# Sport_Analyzer_Teensy4.net
KiCad netlist of a schematic drawn in EAGLE
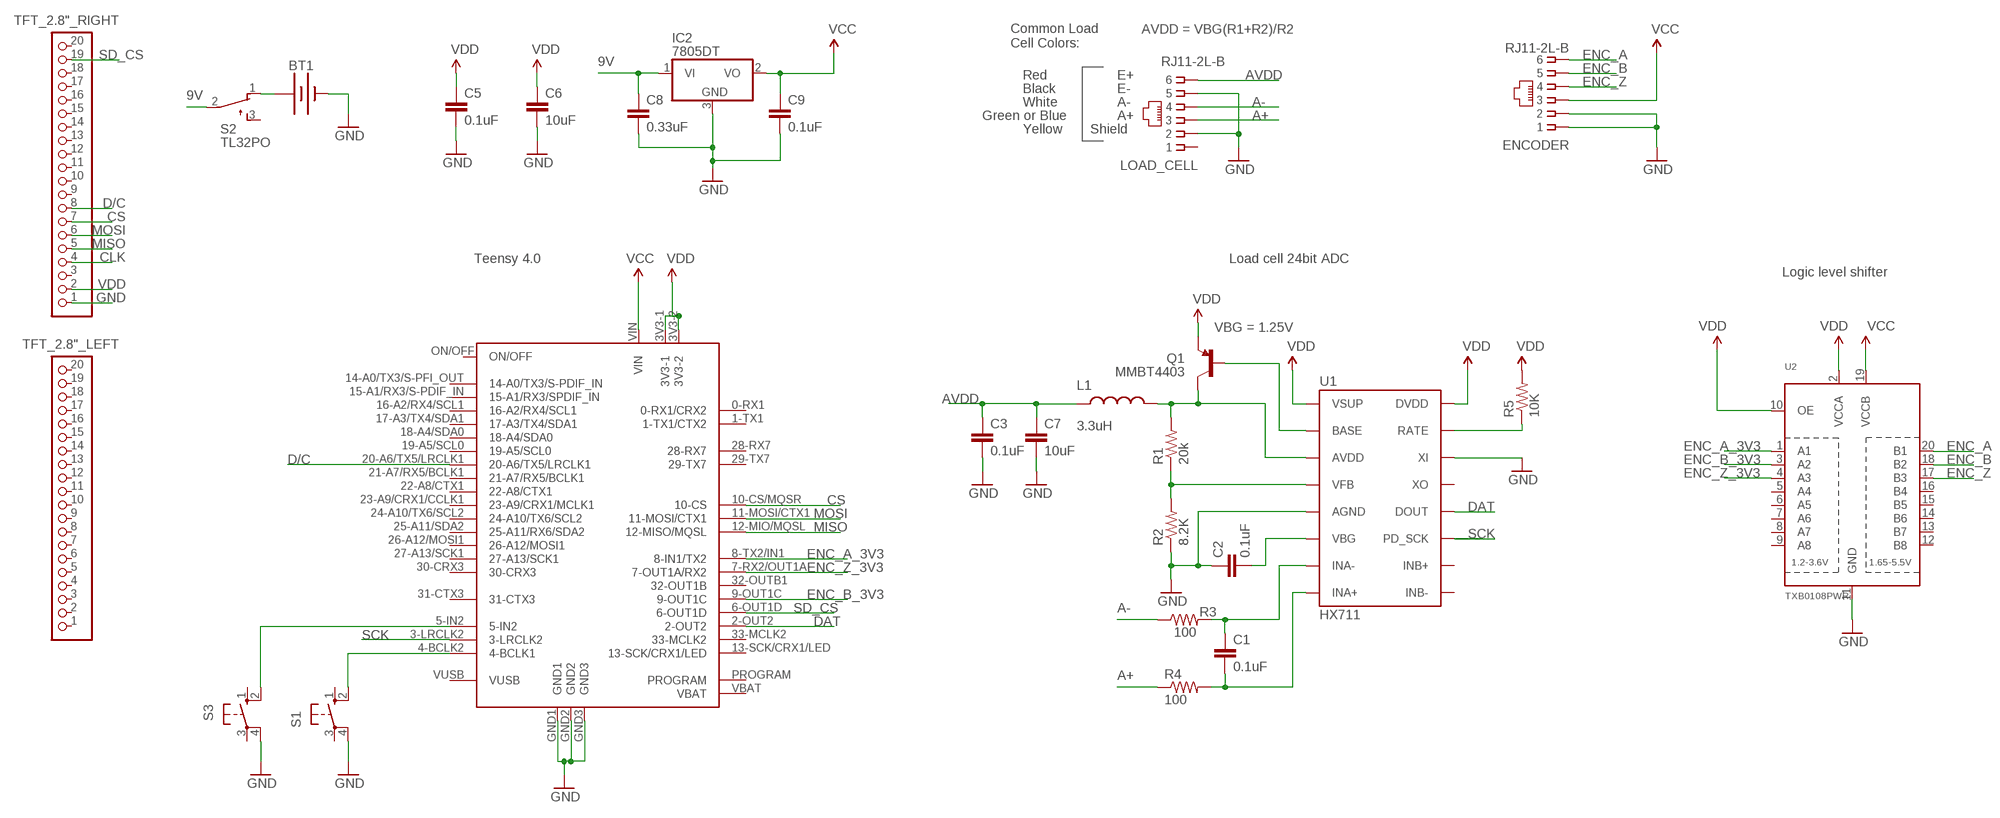
[diagram p0: schematic, sheet 1]

(export (version "E")
  (design (tool "Eeschema 10.0.6"))
  (components
    (comp (ref "BT1")
      (value "BATTERY-9V")
      (footprint "eagle-import:BATTCON_9V")
      (libsource (lib "eagle-import") (part "BATTERY-9V"))
    )
    (comp (ref "C1")
      (value "0.1uF")
      (footprint "eagle-import:0603-CAP")
      (libsource (lib "eagle-import") (part "0.1UF-25V-5%(0603)"))
    )
    (comp (ref "C2")
      (value "0.1uF")
      (footprint "eagle-import:0603-CAP")
      (libsource (lib "eagle-import") (part "0.1UF-25V-5%(0603)"))
    )
    (comp (ref "C3")
      (value "0.1uF")
      (footprint "eagle-import:0603-CAP")
      (libsource (lib "eagle-import") (part "0.1UF-25V-5%(0603)"))
    )
    (comp (ref "C5")
      (value "0.1uF")
      (footprint "eagle-import:0603-CAP")
      (libsource (lib "eagle-import") (part "0.1UF-25V-5%(0603)"))
    )
    (comp (ref "C6")
      (value "10uF")
      (footprint "eagle-import:1210")
      (libsource (lib "eagle-import") (part "10UF50V20%(1210)"))
    )
    (comp (ref "C7")
      (value "10uF")
      (footprint "eagle-import:1210")
      (libsource (lib "eagle-import") (part "10UF50V20%(1210)"))
    )
    (comp (ref "C8")
      (value "0.33uF")
      (footprint "eagle-import:0603-CAP")
      (libsource (lib "eagle-import") (part "0.1UF-25V-5%(0603)"))
    )
    (comp (ref "C9")
      (value "0.1uF")
      (footprint "eagle-import:0603-CAP")
      (libsource (lib "eagle-import") (part "0.1UF-25V-5%(0603)"))
    )
    (comp (ref "ENCODER")
      (value "RJ11-2L-B")
      (footprint "eagle-import:RJ11-NO_SHIELD")
      (fields (field (name "MF") "TYCO ELECTRONICS"))
      (libsource (lib "eagle-import") (part "RJ11-2L-B"))
    )
    (comp (ref "IC2")
      (value "7805DT")
      (footprint "eagle-import:TO252")
      (libsource (lib "eagle-import") (part "78DT05"))
    )
    (comp (ref "L1")
      (value "3.3uH")
      (footprint "eagle-import:0805")
      (libsource (lib "eagle-import") (part "INDUCTOR0805-IND"))
    )
    (comp (ref "LOAD_CELL")
      (value "RJ11-2L-B")
      (footprint "eagle-import:RJ11-NO_SHIELD")
      (fields (field (name "MF") "TYCO ELECTRONICS"))
      (libsource (lib "eagle-import") (part "RJ11-2L-B"))
    )
    (comp (ref "Q1")
      (value "MMBT4403")
      (footprint "eagle-import:SOT23-3")
      (libsource (lib "eagle-import") (part "TRANSISTOR_PNPMMBT4403"))
    )
    (comp (ref "R1")
      (value "20k")
      (footprint "eagle-import:0603-RES")
      (libsource (lib "eagle-import") (part "20KOHM1/10W1%(0603)"))
    )
    (comp (ref "R2")
      (value "8.2K")
      (footprint "eagle-import:0603-RES")
      (libsource (lib "eagle-import") (part "8.2KOHM-1/10W-5%(0603)"))
    )
    (comp (ref "R3")
      (value "100")
      (footprint "eagle-import:0603-RES")
      (libsource (lib "eagle-import") (part "100OHM-1/10W-1%(0603)"))
    )
    (comp (ref "R4")
      (value "100")
      (footprint "eagle-import:0603-RES")
      (libsource (lib "eagle-import") (part "100OHM-1/10W-1%(0603)"))
    )
    (comp (ref "R5")
      (value "10K")
      (footprint "eagle-import:0603-RES")
      (libsource (lib "eagle-import") (part "10KOHM-1/10W-1%(0603)0603"))
    )
    (comp (ref "S1")
      (value "10-XX")
      (footprint "eagle-import:B3F-10XX")
      (fields (field (name "MPN") "B3F-1000"))
      (libsource (lib "eagle-import") (part "10-XX"))
    )
    (comp (ref "S2")
      (value "TL32PO")
      (footprint "eagle-import:TL3XPO")
      (libsource (lib "eagle-import") (part "TL32PO"))
    )
    (comp (ref "S3")
      (value "10-XX")
      (footprint "eagle-import:B3F-10XX")
      (fields (field (name "MPN") "B3F-1000"))
      (libsource (lib "eagle-import") (part "10-XX"))
    )
    (comp (ref "TFT_2.8\"_LEFT")
      (value "PINHD-1X20")
      (footprint "eagle-import:1X20")
      (libsource (lib "eagle-import") (part "PINHD-1X20"))
    )
    (comp (ref "TFT_2.8\"_RIGHT")
      (value "PINHD-1X20")
      (footprint "eagle-import:1X20")
      (libsource (lib "eagle-import") (part "PINHD-1X20"))
    )
    (comp (ref "U$2")
      (value "TEENSY40")
      (footprint "eagle-import:TEENSY40")
      (libsource (lib "eagle-import") (part "TEENSY40"))
    )
    (comp (ref "U1")
      (value "HX711")
      (footprint "eagle-import:SO16")
      (libsource (lib "eagle-import") (part "HX711HX711"))
    )
    (comp (ref "U2")
      (value "TXB0108PWR")
      (footprint "eagle-import:TSSOP20")
      (libsource (lib "eagle-import") (part "TXB0108PWR"))
    )
  )
  (nets
    (net (code "1") (name "/9V") (class "Default")
      (node (ref "C8") (pin "1") (pinfunction "1_1") (pintype "passive"))
      (node (ref "IC2") (pin "1") (pinfunction "VI_1") (pintype "input"))
      (node (ref "S2") (pin "2") (pinfunction "P_2") (pintype "passive"))
    )
    (net (code "2") (name "/A+") (class "Default")
      (node (ref "LOAD_CELL") (pin "3") (pinfunction "3_3") (pintype "passive"))
      (node (ref "R4") (pin "1") (pinfunction "1_1") (pintype "passive"))
    )
    (net (code "3") (name "/A-") (class "Default")
      (node (ref "LOAD_CELL") (pin "4") (pinfunction "4_4") (pintype "passive"))
      (node (ref "R3") (pin "1") (pinfunction "1_1") (pintype "passive"))
    )
    (net (code "4") (name "/AVDD") (class "Default")
      (node (ref "C3") (pin "1") (pinfunction "1_1") (pintype "passive"))
      (node (ref "C7") (pin "1") (pinfunction "1_1") (pintype "passive"))
      (node (ref "L1") (pin "1") (pinfunction "1_1") (pintype "passive"))
      (node (ref "LOAD_CELL") (pin "6") (pinfunction "6_6") (pintype "passive"))
    )
    (net (code "5") (name "/CLK") (class "Default")
      (node (ref "TFT_2.8\"_RIGHT") (pin "4") (pinfunction "4_4") (pintype "passive"))
    )
    (net (code "6") (name "/CS") (class "Default")
      (node (ref "TFT_2.8\"_RIGHT") (pin "7") (pinfunction "7_7") (pintype "passive"))
      (node (ref "U$2") (pin "10-CS/MQSR") (pinfunction "10-CS_10-CS/MQSR") (pintype "bidirectional"))
    )
    (net (code "7") (name "/DAT") (class "Default")
      (node (ref "U$2") (pin "2-OUT2") (pinfunction "2-OUT2_2-OUT2") (pintype "bidirectional"))
      (node (ref "U1") (pin "12") (pinfunction "DOUT_12") (pintype "bidirectional"))
    )
    (net (code "8") (name "/D{slash}C") (class "Default")
      (node (ref "TFT_2.8\"_RIGHT") (pin "8") (pinfunction "8_8") (pintype "passive"))
      (node (ref "U$2") (pin "20-A6/TX5/LRCLK1") (pinfunction "20-A6/TX5/LRCLK1_20-A6/TX5/LRCLK1") (pintype "bidirectional"))
    )
    (net (code "9") (name "/ENC_A") (class "Default")
      (node (ref "ENCODER") (pin "6") (pinfunction "6_6") (pintype "passive"))
      (node (ref "U2") (pin "20") (pinfunction "B1_20") (pintype "bidirectional"))
    )
    (net (code "10") (name "/ENC_A_3V3") (class "Default")
      (node (ref "U$2") (pin "8-TX2/IN1") (pinfunction "8-IN1/TX2_8-TX2/IN1") (pintype "bidirectional"))
      (node (ref "U2") (pin "1") (pinfunction "A1_1") (pintype "bidirectional"))
    )
    (net (code "11") (name "/ENC_B") (class "Default")
      (node (ref "ENCODER") (pin "5") (pinfunction "5_5") (pintype "passive"))
      (node (ref "U2") (pin "18") (pinfunction "B2_18") (pintype "bidirectional"))
    )
    (net (code "12") (name "/ENC_B_3V3") (class "Default")
      (node (ref "U$2") (pin "9-OUT1C") (pinfunction "9-OUT1C_9-OUT1C") (pintype "bidirectional"))
      (node (ref "U2") (pin "3") (pinfunction "A2_3") (pintype "bidirectional"))
    )
    (net (code "13") (name "/ENC_Z") (class "Default")
      (node (ref "ENCODER") (pin "4") (pinfunction "4_4") (pintype "passive"))
      (node (ref "U2") (pin "17") (pinfunction "B3_17") (pintype "bidirectional"))
    )
    (net (code "14") (name "/ENC_Z_3V3") (class "Default")
      (node (ref "U$2") (pin "7-RX2/OUT1A") (pinfunction "7-OUT1A/RX2_7-RX2/OUT1A") (pintype "bidirectional"))
      (node (ref "U2") (pin "4") (pinfunction "A3_4") (pintype "bidirectional"))
    )
    (net (code "15") (name "/MISO") (class "Default")
      (node (ref "TFT_2.8\"_RIGHT") (pin "5") (pinfunction "5_5") (pintype "passive"))
      (node (ref "U$2") (pin "12-MIO/MQSL") (pinfunction "12-MISO/MQSL_12-MIO/MQSL") (pintype "bidirectional"))
    )
    (net (code "16") (name "/MOSI") (class "Default")
      (node (ref "TFT_2.8\"_RIGHT") (pin "6") (pinfunction "6_6") (pintype "passive"))
      (node (ref "U$2") (pin "11-MOSI/CTX1") (pinfunction "11-MOSI/CTX1_11-MOSI/CTX1") (pintype "bidirectional"))
    )
    (net (code "17") (name "/SCK") (class "Default")
      (node (ref "U$2") (pin "3-LRCLK2") (pinfunction "3-LRCLK2_3-LRCLK2") (pintype "bidirectional"))
      (node (ref "U1") (pin "11") (pinfunction "PD_SCK_11") (pintype "bidirectional"))
    )
    (net (code "18") (name "/SD_CS") (class "Default")
      (node (ref "TFT_2.8\"_RIGHT") (pin "19") (pinfunction "19_19") (pintype "passive"))
      (node (ref "U$2") (pin "6-OUT1D") (pinfunction "6-OUT1D_6-OUT1D") (pintype "bidirectional"))
    )
    (net (code "19") (name "GND") (class "Default")
      (node (ref "BT1") (pin "-") (pinfunction "-_-") (pintype "power_in"))
      (node (ref "C2") (pin "1") (pinfunction "1_1") (pintype "passive"))
      (node (ref "C3") (pin "2") (pinfunction "2_2") (pintype "passive"))
      (node (ref "C5") (pin "2") (pinfunction "2_2") (pintype "passive"))
      (node (ref "C6") (pin "2") (pinfunction "2_2") (pintype "passive"))
      (node (ref "C7") (pin "2") (pinfunction "2_2") (pintype "passive"))
      (node (ref "C8") (pin "2") (pinfunction "2_2") (pintype "passive"))
      (node (ref "C9") (pin "2") (pinfunction "2_2") (pintype "passive"))
      (node (ref "ENCODER") (pin "1") (pinfunction "1_1") (pintype "passive"))
      (node (ref "ENCODER") (pin "2") (pinfunction "2_2") (pintype "passive"))
      (node (ref "IC2") (pin "3") (pinfunction "GND_3") (pintype "passive"))
      (node (ref "LOAD_CELL") (pin "2") (pinfunction "2_2") (pintype "passive"))
      (node (ref "LOAD_CELL") (pin "5") (pinfunction "5_5") (pintype "passive"))
      (node (ref "R2") (pin "1") (pinfunction "1_1") (pintype "passive"))
      (node (ref "S1") (pin "4") (pinfunction "P1_4") (pintype "passive"))
      (node (ref "S3") (pin "4") (pinfunction "P1_4") (pintype "passive"))
      (node (ref "TFT_2.8\"_RIGHT") (pin "1") (pinfunction "1_1") (pintype "passive"))
      (node (ref "U$2") (pin "GND1") (pinfunction "GND1_GND1") (pintype "bidirectional"))
      (node (ref "U$2") (pin "GND2") (pinfunction "GND2_GND2") (pintype "bidirectional"))
      (node (ref "U$2") (pin "GND3") (pinfunction "GND3_GND3") (pintype "bidirectional"))
      (node (ref "U1") (pin "14") (pinfunction "XI_14") (pintype "bidirectional"))
      (node (ref "U1") (pin "5") (pinfunction "AGND_5") (pintype "bidirectional"))
      (node (ref "U2") (pin "11") (pinfunction "GND_11") (pintype "bidirectional"))
    )
    (net (code "20") (name "Net-(Q1-B)") (class "Default")
      (node (ref "Q1") (pin "1") (pinfunction "B_1") (pintype "passive"))
      (node (ref "U1") (pin "2") (pinfunction "BASE_2") (pintype "bidirectional"))
    )
    (net (code "21") (name "Net-(Q1-C)") (class "Default")
      (node (ref "L1") (pin "2") (pinfunction "2_2") (pintype "passive"))
      (node (ref "Q1") (pin "3") (pinfunction "C_3") (pintype "passive"))
      (node (ref "R1") (pin "2") (pinfunction "2_2") (pintype "passive"))
      (node (ref "U1") (pin "3") (pinfunction "AVDD_3") (pintype "bidirectional"))
    )
    (net (code "22") (name "Net-(S1-S1)") (class "Default")
      (node (ref "S1") (pin "2") (pinfunction "S1_2") (pintype "passive"))
      (node (ref "U$2") (pin "4-BCLK2") (pinfunction "4-BCLK1_4-BCLK2") (pintype "bidirectional"))
    )
    (net (code "23") (name "Net-(S2-O)") (class "Default")
      (node (ref "BT1") (pin "+") (pinfunction "+_+") (pintype "power_in"))
      (node (ref "S2") (pin "1") (pinfunction "O_1") (pintype "passive"))
    )
    (net (code "24") (name "Net-(S3-S1)") (class "Default")
      (node (ref "S3") (pin "2") (pinfunction "S1_2") (pintype "passive"))
      (node (ref "U$2") (pin "5-IN2") (pinfunction "5-IN2_5-IN2") (pintype "bidirectional"))
    )
    (net (code "25") (name "Net-(U1-INA+)") (class "Default")
      (node (ref "C1") (pin "2") (pinfunction "2_2") (pintype "passive"))
      (node (ref "R4") (pin "2") (pinfunction "2_2") (pintype "passive"))
      (node (ref "U1") (pin "8") (pinfunction "INA+_8") (pintype "bidirectional"))
    )
    (net (code "26") (name "Net-(U1-INA-)") (class "Default")
      (node (ref "C1") (pin "1") (pinfunction "1_1") (pintype "passive"))
      (node (ref "R3") (pin "2") (pinfunction "2_2") (pintype "passive"))
      (node (ref "U1") (pin "7") (pinfunction "INA-_7") (pintype "bidirectional"))
    )
    (net (code "27") (name "Net-(U1-RATE)") (class "Default")
      (node (ref "R5") (pin "1") (pinfunction "1_1") (pintype "passive"))
      (node (ref "U1") (pin "15") (pinfunction "RATE_15") (pintype "bidirectional"))
    )
    (net (code "28") (name "Net-(U1-VBG)") (class "Default")
      (node (ref "C2") (pin "2") (pinfunction "2_2") (pintype "passive"))
      (node (ref "U1") (pin "6") (pinfunction "VBG_6") (pintype "bidirectional"))
    )
    (net (code "29") (name "Net-(U1-VFB)") (class "Default")
      (node (ref "R1") (pin "1") (pinfunction "1_1") (pintype "passive"))
      (node (ref "R2") (pin "2") (pinfunction "2_2") (pintype "passive"))
      (node (ref "U1") (pin "4") (pinfunction "VFB_4") (pintype "bidirectional"))
    )
    (net (code "30") (name "VCC") (class "Default")
      (node (ref "C9") (pin "1") (pinfunction "1_1") (pintype "passive"))
      (node (ref "ENCODER") (pin "3") (pinfunction "3_3") (pintype "passive"))
      (node (ref "IC2") (pin "2") (pinfunction "VO_2") (pintype "passive"))
      (node (ref "U$2") (pin "VIN") (pinfunction "VIN_VIN") (pintype "bidirectional"))
      (node (ref "U2") (pin "19") (pinfunction "VCCB_19") (pintype "bidirectional"))
    )
    (net (code "31") (name "VDD") (class "Default")
      (node (ref "C5") (pin "1") (pinfunction "1_1") (pintype "passive"))
      (node (ref "C6") (pin "1") (pinfunction "1_1") (pintype "passive"))
      (node (ref "Q1") (pin "2") (pinfunction "E_2") (pintype "passive"))
      (node (ref "R5") (pin "2") (pinfunction "2_2") (pintype "passive"))
      (node (ref "TFT_2.8\"_RIGHT") (pin "2") (pinfunction "2_2") (pintype "passive"))
      (node (ref "U$2") (pin "3V3-1") (pinfunction "3V3-1_3V3-1") (pintype "bidirectional"))
      (node (ref "U$2") (pin "3V3-2") (pinfunction "3V3-2_3V3-2") (pintype "bidirectional"))
      (node (ref "U1") (pin "1") (pinfunction "VSUP_1") (pintype "bidirectional"))
      (node (ref "U1") (pin "16") (pinfunction "DVDD_16") (pintype "bidirectional"))
      (node (ref "U2") (pin "10") (pinfunction "OE_10") (pintype "bidirectional"))
      (node (ref "U2") (pin "2") (pinfunction "VCCA_2") (pintype "bidirectional"))
    )
    (net (code "32") (name "unconnected-(LOAD_CELL-Pad1)") (class "Default")
      (node (ref "LOAD_CELL") (pin "1") (pinfunction "1_1") (pintype "passive"))
    )
    (net (code "33") (name "unconnected-(S1-P-Pad3)") (class "Default")
      (node (ref "S1") (pin "3") (pinfunction "P_3") (pintype "passive"))
    )
    (net (code "34") (name "unconnected-(S1-S-Pad1)") (class "Default")
      (node (ref "S1") (pin "1") (pinfunction "S_1") (pintype "passive"))
    )
    (net (code "35") (name "unconnected-(S2-S-Pad3)") (class "Default")
      (node (ref "S2") (pin "3") (pinfunction "S_3") (pintype "passive"))
    )
    (net (code "36") (name "unconnected-(S3-P-Pad3)") (class "Default")
      (node (ref "S3") (pin "3") (pinfunction "P_3") (pintype "passive"))
    )
    (net (code "37") (name "unconnected-(S3-S-Pad1)") (class "Default")
      (node (ref "S3") (pin "1") (pinfunction "S_1") (pintype "passive"))
    )
    (net (code "38") (name "unconnected-(TFT_2.8\"_LEFT-Pad1)") (class "Default")
      (node (ref "TFT_2.8\"_LEFT") (pin "1") (pinfunction "1_1") (pintype "passive"))
    )
    (net (code "39") (name "unconnected-(TFT_2.8\"_LEFT-Pad2)") (class "Default")
      (node (ref "TFT_2.8\"_LEFT") (pin "2") (pinfunction "2_2") (pintype "passive"))
    )
    (net (code "40") (name "unconnected-(TFT_2.8\"_LEFT-Pad3)") (class "Default")
      (node (ref "TFT_2.8\"_LEFT") (pin "3") (pinfunction "3_3") (pintype "passive"))
    )
    (net (code "41") (name "unconnected-(TFT_2.8\"_LEFT-Pad4)") (class "Default")
      (node (ref "TFT_2.8\"_LEFT") (pin "4") (pinfunction "4_4") (pintype "passive"))
    )
    (net (code "42") (name "unconnected-(TFT_2.8\"_LEFT-Pad5)") (class "Default")
      (node (ref "TFT_2.8\"_LEFT") (pin "5") (pinfunction "5_5") (pintype "passive"))
    )
    (net (code "43") (name "unconnected-(TFT_2.8\"_LEFT-Pad6)") (class "Default")
      (node (ref "TFT_2.8\"_LEFT") (pin "6") (pinfunction "6_6") (pintype "passive"))
    )
    (net (code "44") (name "unconnected-(TFT_2.8\"_LEFT-Pad7)") (class "Default")
      (node (ref "TFT_2.8\"_LEFT") (pin "7") (pinfunction "7_7") (pintype "passive"))
    )
    (net (code "45") (name "unconnected-(TFT_2.8\"_LEFT-Pad8)") (class "Default")
      (node (ref "TFT_2.8\"_LEFT") (pin "8") (pinfunction "8_8") (pintype "passive"))
    )
    (net (code "46") (name "unconnected-(TFT_2.8\"_LEFT-Pad9)") (class "Default")
      (node (ref "TFT_2.8\"_LEFT") (pin "9") (pinfunction "9_9") (pintype "passive"))
    )
    (net (code "47") (name "unconnected-(TFT_2.8\"_LEFT-Pad10)") (class "Default")
      (node (ref "TFT_2.8\"_LEFT") (pin "10") (pinfunction "10_10") (pintype "passive"))
    )
    (net (code "48") (name "unconnected-(TFT_2.8\"_LEFT-Pad11)") (class "Default")
      (node (ref "TFT_2.8\"_LEFT") (pin "11") (pinfunction "11_11") (pintype "passive"))
    )
    (net (code "49") (name "unconnected-(TFT_2.8\"_LEFT-Pad12)") (class "Default")
      (node (ref "TFT_2.8\"_LEFT") (pin "12") (pinfunction "12_12") (pintype "passive"))
    )
    (net (code "50") (name "unconnected-(TFT_2.8\"_LEFT-Pad13)") (class "Default")
      (node (ref "TFT_2.8\"_LEFT") (pin "13") (pinfunction "13_13") (pintype "passive"))
    )
    (net (code "51") (name "unconnected-(TFT_2.8\"_LEFT-Pad14)") (class "Default")
      (node (ref "TFT_2.8\"_LEFT") (pin "14") (pinfunction "14_14") (pintype "passive"))
    )
    (net (code "52") (name "unconnected-(TFT_2.8\"_LEFT-Pad15)") (class "Default")
      (node (ref "TFT_2.8\"_LEFT") (pin "15") (pinfunction "15_15") (pintype "passive"))
    )
    (net (code "53") (name "unconnected-(TFT_2.8\"_LEFT-Pad16)") (class "Default")
      (node (ref "TFT_2.8\"_LEFT") (pin "16") (pinfunction "16_16") (pintype "passive"))
    )
    (net (code "54") (name "unconnected-(TFT_2.8\"_LEFT-Pad17)") (class "Default")
      (node (ref "TFT_2.8\"_LEFT") (pin "17") (pinfunction "17_17") (pintype "passive"))
    )
    (net (code "55") (name "unconnected-(TFT_2.8\"_LEFT-Pad18)") (class "Default")
      (node (ref "TFT_2.8\"_LEFT") (pin "18") (pinfunction "18_18") (pintype "passive"))
    )
    (net (code "56") (name "unconnected-(TFT_2.8\"_LEFT-Pad19)") (class "Default")
      (node (ref "TFT_2.8\"_LEFT") (pin "19") (pinfunction "19_19") (pintype "passive"))
    )
    (net (code "57") (name "unconnected-(TFT_2.8\"_LEFT-Pad20)") (class "Default")
      (node (ref "TFT_2.8\"_LEFT") (pin "20") (pinfunction "20_20") (pintype "passive"))
    )
    (net (code "58") (name "unconnected-(TFT_2.8\"_RIGHT-Pad3)") (class "Default")
      (node (ref "TFT_2.8\"_RIGHT") (pin "3") (pinfunction "3_3") (pintype "passive"))
    )
    (net (code "59") (name "unconnected-(TFT_2.8\"_RIGHT-Pad9)") (class "Default")
      (node (ref "TFT_2.8\"_RIGHT") (pin "9") (pinfunction "9_9") (pintype "passive"))
    )
    (net (code "60") (name "unconnected-(TFT_2.8\"_RIGHT-Pad10)") (class "Default")
      (node (ref "TFT_2.8\"_RIGHT") (pin "10") (pinfunction "10_10") (pintype "passive"))
    )
    (net (code "61") (name "unconnected-(TFT_2.8\"_RIGHT-Pad11)") (class "Default")
      (node (ref "TFT_2.8\"_RIGHT") (pin "11") (pinfunction "11_11") (pintype "passive"))
    )
    (net (code "62") (name "unconnected-(TFT_2.8\"_RIGHT-Pad12)") (class "Default")
      (node (ref "TFT_2.8\"_RIGHT") (pin "12") (pinfunction "12_12") (pintype "passive"))
    )
    (net (code "63") (name "unconnected-(TFT_2.8\"_RIGHT-Pad13)") (class "Default")
      (node (ref "TFT_2.8\"_RIGHT") (pin "13") (pinfunction "13_13") (pintype "passive"))
    )
    (net (code "64") (name "unconnected-(TFT_2.8\"_RIGHT-Pad14)") (class "Default")
      (node (ref "TFT_2.8\"_RIGHT") (pin "14") (pinfunction "14_14") (pintype "passive"))
    )
    (net (code "65") (name "unconnected-(TFT_2.8\"_RIGHT-Pad15)") (class "Default")
      (node (ref "TFT_2.8\"_RIGHT") (pin "15") (pinfunction "15_15") (pintype "passive"))
    )
    (net (code "66") (name "unconnected-(TFT_2.8\"_RIGHT-Pad16)") (class "Default")
      (node (ref "TFT_2.8\"_RIGHT") (pin "16") (pinfunction "16_16") (pintype "passive"))
    )
    (net (code "67") (name "unconnected-(TFT_2.8\"_RIGHT-Pad17)") (class "Default")
      (node (ref "TFT_2.8\"_RIGHT") (pin "17") (pinfunction "17_17") (pintype "passive"))
    )
    (net (code "68") (name "unconnected-(TFT_2.8\"_RIGHT-Pad18)") (class "Default")
      (node (ref "TFT_2.8\"_RIGHT") (pin "18") (pinfunction "18_18") (pintype "passive"))
    )
    (net (code "69") (name "unconnected-(TFT_2.8\"_RIGHT-Pad20)") (class "Default")
      (node (ref "TFT_2.8\"_RIGHT") (pin "20") (pinfunction "20_20") (pintype "passive"))
    )
    (net (code "70") (name "unconnected-(U$2-0-RX1{slash}CRX2-Pad0-RX1)") (class "Default")
      (node (ref "U$2") (pin "0-RX1") (pinfunction "0-RX1/CRX2_0-RX1") (pintype "bidirectional"))
    )
    (net (code "71") (name "unconnected-(U$2-1-TX1{slash}CTX2-Pad1-TX1)") (class "Default")
      (node (ref "U$2") (pin "1-TX1") (pinfunction "1-TX1/CTX2_1-TX1") (pintype "bidirectional"))
    )
    (net (code "72") (name "unconnected-(U$2-14-A0{slash}TX3{slash}S-PDIF_IN-Pad14-A0{slash}TX3{slash}S-PFI_OUT)") (class "Default")
      (node (ref "U$2") (pin "14-A0/TX3/S-PFI_OUT") (pinfunction "14-A0/TX3/S-PDIF_IN_14-A0/TX3/S-PFI_OUT") (pintype "bidirectional"))
    )
    (net (code "73") (name "unconnected-(U$2-15-A1{slash}RX3{slash}SPDIF_IN-Pad15-A1{slash}RX3{slash}S-PDIF_IN)") (class "Default")
      (node (ref "U$2") (pin "15-A1/RX3/S-PDIF_IN") (pinfunction "15-A1/RX3/SPDIF_IN_15-A1/RX3/S-PDIF_IN") (pintype "bidirectional"))
    )
    (net (code "74") (name "unconnected-(U$2-23-A9{slash}CRX1{slash}MCLK1-Pad23-A9{slash}CRX1{slash}CCLK1)") (class "Default")
      (node (ref "U$2") (pin "23-A9/CRX1/CCLK1") (pinfunction "23-A9/CRX1/MCLK1_23-A9/CRX1/CCLK1") (pintype "bidirectional"))
    )
    (net (code "75") (name "unconnected-(U$2-25-A11{slash}RX6{slash}SDA2-Pad25-A11{slash}SDA2)") (class "Default")
      (node (ref "U$2") (pin "25-A11/SDA2") (pinfunction "25-A11/RX6/SDA2_25-A11/SDA2") (pintype "bidirectional"))
    )
    (net (code "76") (name "unconnected-(U$2-32-OUT1B-Pad32-OUTB1)") (class "Default")
      (node (ref "U$2") (pin "32-OUTB1") (pinfunction "32-OUT1B_32-OUTB1") (pintype "bidirectional"))
    )
    (net (code "77") (name "unconnected-(U$2-Pad13-SCK{slash}CRX1{slash}LED)") (class "Default")
      (node (ref "U$2") (pin "13-SCK/CRX1/LED") (pinfunction "13-SCK/CRX1/LED_13-SCK/CRX1/LED") (pintype "bidirectional"))
    )
    (net (code "78") (name "unconnected-(U$2-Pad16-A2{slash}RX4{slash}SCL1)") (class "Default")
      (node (ref "U$2") (pin "16-A2/RX4/SCL1") (pinfunction "16-A2/RX4/SCL1_16-A2/RX4/SCL1") (pintype "bidirectional"))
    )
    (net (code "79") (name "unconnected-(U$2-Pad17-A3{slash}TX4{slash}SDA1)") (class "Default")
      (node (ref "U$2") (pin "17-A3/TX4/SDA1") (pinfunction "17-A3/TX4/SDA1_17-A3/TX4/SDA1") (pintype "bidirectional"))
    )
    (net (code "80") (name "unconnected-(U$2-Pad18-A4{slash}SDA0)") (class "Default")
      (node (ref "U$2") (pin "18-A4/SDA0") (pinfunction "18-A4/SDA0_18-A4/SDA0") (pintype "bidirectional"))
    )
    (net (code "81") (name "unconnected-(U$2-Pad19-A5{slash}SCL0)") (class "Default")
      (node (ref "U$2") (pin "19-A5/SCL0") (pinfunction "19-A5/SCL0_19-A5/SCL0") (pintype "bidirectional"))
    )
    (net (code "82") (name "unconnected-(U$2-Pad21-A7{slash}RX5{slash}BCLK1)") (class "Default")
      (node (ref "U$2") (pin "21-A7/RX5/BCLK1") (pinfunction "21-A7/RX5/BCLK1_21-A7/RX5/BCLK1") (pintype "bidirectional"))
    )
    (net (code "83") (name "unconnected-(U$2-Pad22-A8{slash}CTX1)") (class "Default")
      (node (ref "U$2") (pin "22-A8/CTX1") (pinfunction "22-A8/CTX1_22-A8/CTX1") (pintype "bidirectional"))
    )
    (net (code "84") (name "unconnected-(U$2-Pad24-A10{slash}TX6{slash}SCL2)") (class "Default")
      (node (ref "U$2") (pin "24-A10/TX6/SCL2") (pinfunction "24-A10/TX6/SCL2_24-A10/TX6/SCL2") (pintype "bidirectional"))
    )
    (net (code "85") (name "unconnected-(U$2-Pad26-A12{slash}MOSI1)") (class "Default")
      (node (ref "U$2") (pin "26-A12/MOSI1") (pinfunction "26-A12/MOSI1_26-A12/MOSI1") (pintype "bidirectional"))
    )
    (net (code "86") (name "unconnected-(U$2-Pad27-A13{slash}SCK1)") (class "Default")
      (node (ref "U$2") (pin "27-A13/SCK1") (pinfunction "27-A13/SCK1_27-A13/SCK1") (pintype "bidirectional"))
    )
    (net (code "87") (name "unconnected-(U$2-Pad28-RX7)") (class "Default")
      (node (ref "U$2") (pin "28-RX7") (pinfunction "28-RX7_28-RX7") (pintype "bidirectional"))
    )
    (net (code "88") (name "unconnected-(U$2-Pad29-TX7)") (class "Default")
      (node (ref "U$2") (pin "29-TX7") (pinfunction "29-TX7_29-TX7") (pintype "bidirectional"))
    )
    (net (code "89") (name "unconnected-(U$2-Pad30-CRX3)") (class "Default")
      (node (ref "U$2") (pin "30-CRX3") (pinfunction "30-CRX3_30-CRX3") (pintype "bidirectional"))
    )
    (net (code "90") (name "unconnected-(U$2-Pad31-CTX3)") (class "Default")
      (node (ref "U$2") (pin "31-CTX3") (pinfunction "31-CTX3_31-CTX3") (pintype "bidirectional"))
    )
    (net (code "91") (name "unconnected-(U$2-Pad33-MCLK2)") (class "Default")
      (node (ref "U$2") (pin "33-MCLK2") (pinfunction "33-MCLK2_33-MCLK2") (pintype "bidirectional"))
    )
    (net (code "92") (name "unconnected-(U$2-PadON{slash}OFF)") (class "Default")
      (node (ref "U$2") (pin "ON/OFF") (pinfunction "ON/OFF_ON/OFF") (pintype "bidirectional"))
    )
    (net (code "93") (name "unconnected-(U$2-PadPROGRAM)") (class "Default")
      (node (ref "U$2") (pin "PROGRAM") (pinfunction "PROGRAM_PROGRAM") (pintype "bidirectional"))
    )
    (net (code "94") (name "unconnected-(U$2-PadVBAT)") (class "Default")
      (node (ref "U$2") (pin "VBAT") (pinfunction "VBAT_VBAT") (pintype "bidirectional"))
    )
    (net (code "95") (name "unconnected-(U$2-PadVUSB)") (class "Default")
      (node (ref "U$2") (pin "VUSB") (pinfunction "VUSB_VUSB") (pintype "bidirectional"))
    )
    (net (code "96") (name "unconnected-(U1-INB+-Pad10)") (class "Default")
      (node (ref "U1") (pin "10") (pinfunction "INB+_10") (pintype "bidirectional"))
    )
    (net (code "97") (name "unconnected-(U1-INB--Pad9)") (class "Default")
      (node (ref "U1") (pin "9") (pinfunction "INB-_9") (pintype "bidirectional"))
    )
    (net (code "98") (name "unconnected-(U1-XO-Pad13)") (class "Default")
      (node (ref "U1") (pin "13") (pinfunction "XO_13") (pintype "bidirectional"))
    )
    (net (code "99") (name "unconnected-(U2-A4-Pad5)") (class "Default")
      (node (ref "U2") (pin "5") (pinfunction "A4_5") (pintype "bidirectional"))
    )
    (net (code "100") (name "unconnected-(U2-A5-Pad6)") (class "Default")
      (node (ref "U2") (pin "6") (pinfunction "A5_6") (pintype "bidirectional"))
    )
    (net (code "101") (name "unconnected-(U2-A6-Pad7)") (class "Default")
      (node (ref "U2") (pin "7") (pinfunction "A6_7") (pintype "bidirectional"))
    )
    (net (code "102") (name "unconnected-(U2-A7-Pad8)") (class "Default")
      (node (ref "U2") (pin "8") (pinfunction "A7_8") (pintype "bidirectional"))
    )
    (net (code "103") (name "unconnected-(U2-A8-Pad9)") (class "Default")
      (node (ref "U2") (pin "9") (pinfunction "A8_9") (pintype "bidirectional"))
    )
    (net (code "104") (name "unconnected-(U2-B4-Pad16)") (class "Default")
      (node (ref "U2") (pin "16") (pinfunction "B4_16") (pintype "bidirectional"))
    )
    (net (code "105") (name "unconnected-(U2-B5-Pad15)") (class "Default")
      (node (ref "U2") (pin "15") (pinfunction "B5_15") (pintype "bidirectional"))
    )
    (net (code "106") (name "unconnected-(U2-B6-Pad14)") (class "Default")
      (node (ref "U2") (pin "14") (pinfunction "B6_14") (pintype "bidirectional"))
    )
    (net (code "107") (name "unconnected-(U2-B7-Pad13)") (class "Default")
      (node (ref "U2") (pin "13") (pinfunction "B7_13") (pintype "bidirectional"))
    )
    (net (code "108") (name "unconnected-(U2-B8-Pad12)") (class "Default")
      (node (ref "U2") (pin "12") (pinfunction "B8_12") (pintype "bidirectional"))
    )
  )
)
